# Lora_G_v1_3.net
KiCad netlist of a schematic drawn in EAGLE
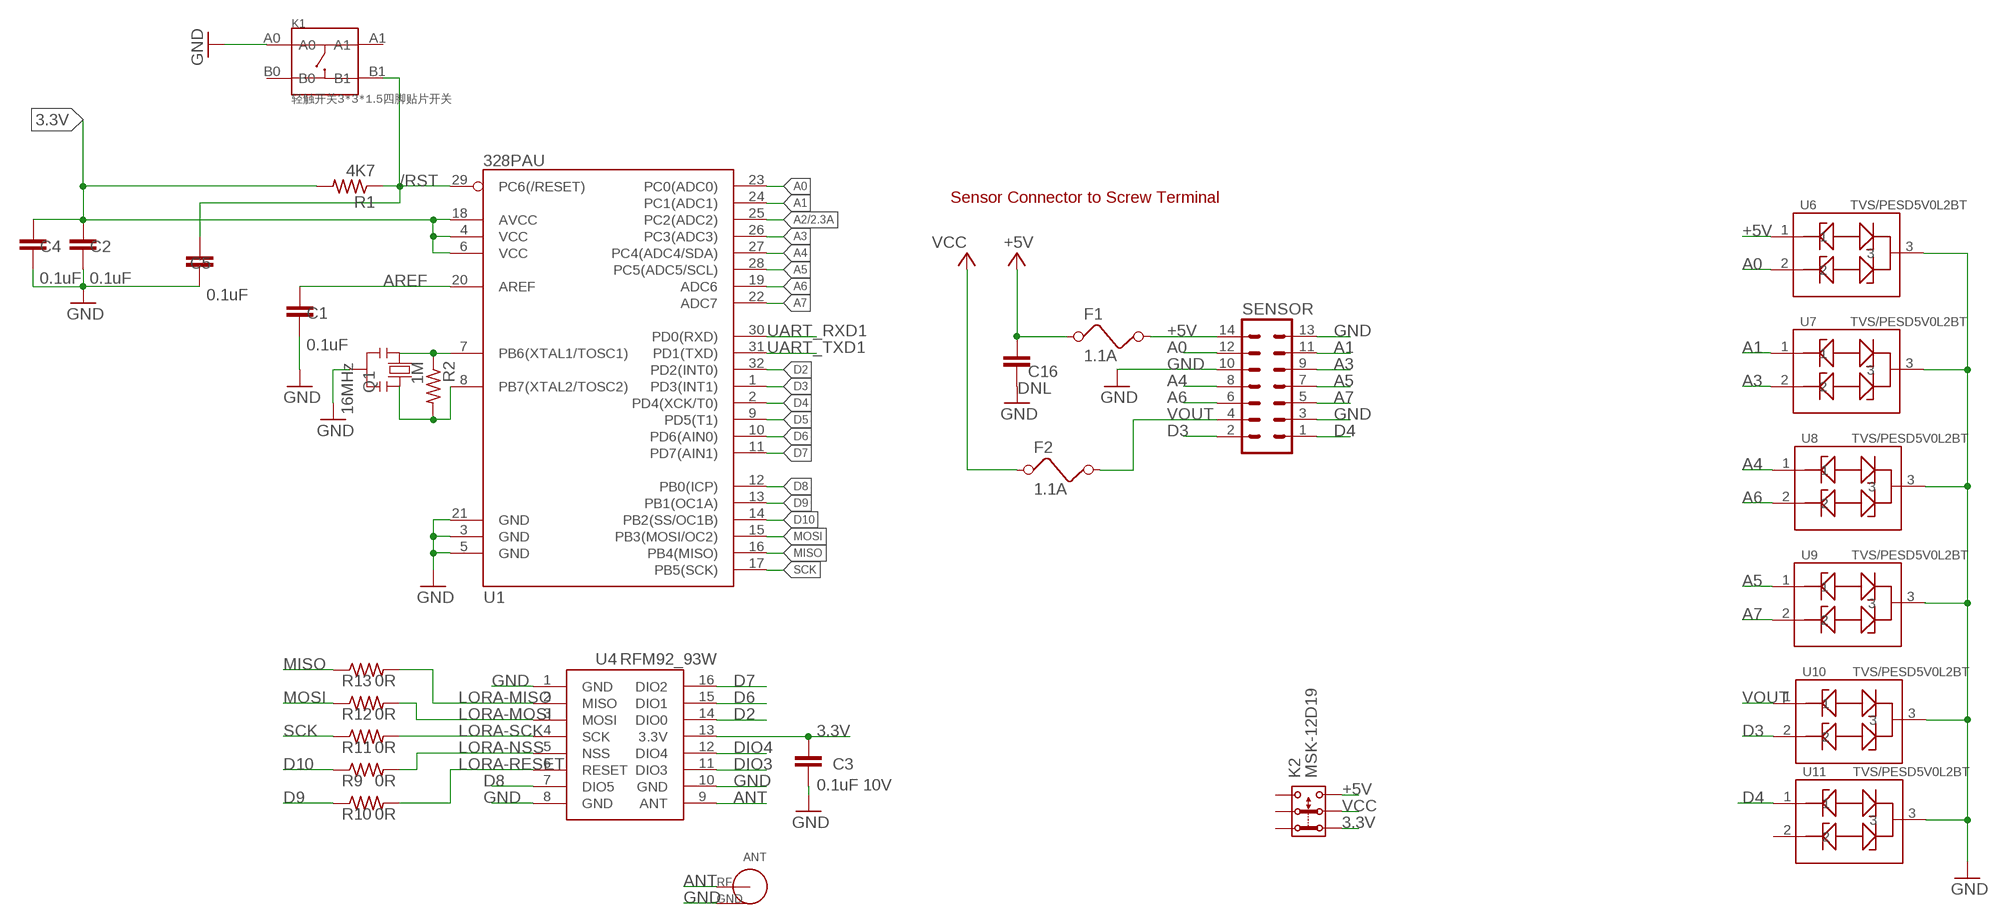
[diagram p0: schematic, sheet 1]
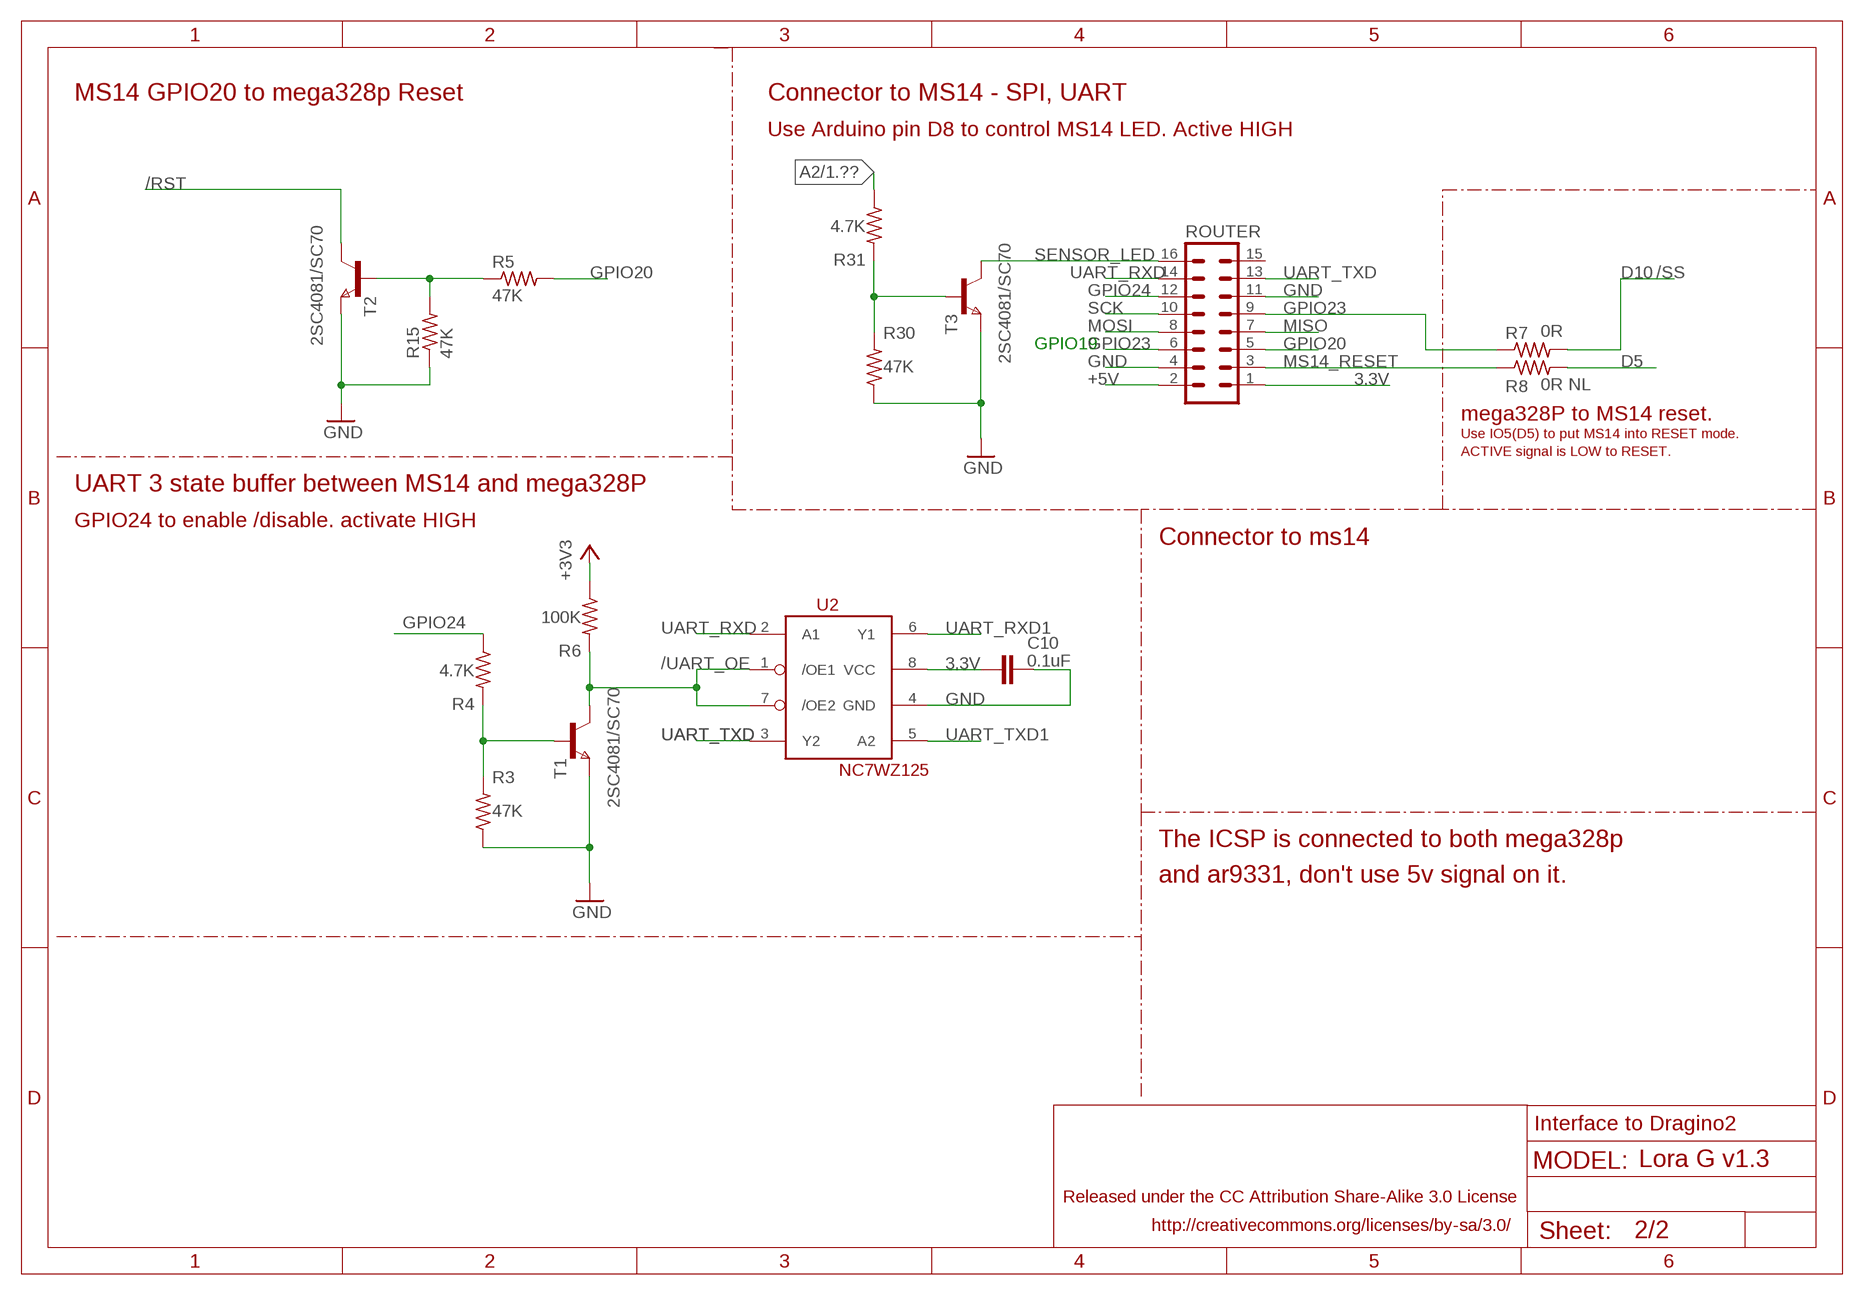
[diagram p1: schematic, sheet 2]

(export (version "E")
  (design (tool "Eeschema 10.0.6"))
  (components
    (comp (ref "C10")
      (value "0.1uF")
      (footprint "eagle-import:C0402")
      (libsource (lib "eagle-import") (part "C-EUC0402"))
    )
    (comp (ref "R3")
      (value "47K")
      (footprint "eagle-import:R0402")
      (libsource (lib "eagle-import") (part "R-US_R0402"))
    )
    (comp (ref "R4")
      (value "4.7K")
      (footprint "eagle-import:R0402")
      (libsource (lib "eagle-import") (part "R-US_R0402"))
    )
    (comp (ref "R5")
      (value "47K")
      (footprint "eagle-import:R0402")
      (libsource (lib "eagle-import") (part "R-US_R0402"))
    )
    (comp (ref "R6")
      (value "100K")
      (footprint "eagle-import:R0402")
      (libsource (lib "eagle-import") (part "R-US_R0402"))
    )
    (comp (ref "R7")
      (value "0R")
      (footprint "eagle-import:R0402")
      (libsource (lib "eagle-import") (part "R-US_R0402"))
    )
    (comp (ref "R8")
      (value "0R NL")
      (footprint "eagle-import:R0805")
      (libsource (lib "eagle-import") (part "R-US_R0805"))
    )
    (comp (ref "R15")
      (value "47K")
      (footprint "eagle-import:R0402")
      (libsource (lib "eagle-import") (part "R-US_R0402"))
    )
    (comp (ref "R30")
      (value "47K")
      (footprint "eagle-import:R0402")
      (libsource (lib "eagle-import") (part "R-US_R0402"))
    )
    (comp (ref "R31")
      (value "4.7K")
      (footprint "eagle-import:R0402")
      (libsource (lib "eagle-import") (part "R-US_R0402"))
    )
    (comp (ref "ROUTER")
      (value "MA08-2")
      (footprint "eagle-import:MA08-2")
      (libsource (lib "eagle-import") (part "MA08-2"))
    )
    (comp (ref "T1")
      (value "2SC4081/SC70")
      (footprint "eagle-import:SOT323")
      (fields (field (name "MPN") "DSS4160U-7"))
      (libsource (lib "eagle-import") (part "NPNSOT323"))
    )
    (comp (ref "T2")
      (value "2SC4081/SC70")
      (footprint "eagle-import:SOT323")
      (fields
        (field (name "MPN") "DSS4160U-7")
        (field (name "MPN_1") "DSS4160U-7")
        (field (name "OC_FARNELL") "1710696")
        (field (name "OC_NEWARK") "25R4558")
      )
      (libsource (lib "eagle-import") (part "NPNSOT323"))
    )
    (comp (ref "T3")
      (value "2SC4081/SC70")
      (footprint "eagle-import:SOT323")
      (fields (field (name "MPN") "DSS4160U-7"))
      (libsource (lib "eagle-import") (part "NPNSOT323"))
    )
    (comp (ref "U2")
      (value "NC7WZ125")
      (footprint "eagle-import:US8")
      (libsource (lib "eagle-import") (part "NC7WZ125"))
    )
    (comp (ref "ANT")
      (value "I-PEX")
      (footprint "eagle-import:I-PEX")
      (libsource (lib "eagle-import") (part "I-PEX"))
    )
    (comp (ref "C1")
      (value "0.1uF")
      (footprint "eagle-import:C0402")
      (libsource (lib "eagle-import") (part "dragino-passive_C-EUC0402"))
    )
    (comp (ref "C2")
      (value "0.1uF")
      (footprint "eagle-import:C0402")
      (libsource (lib "eagle-import") (part "dragino-passive_C-EUC0402"))
    )
    (comp (ref "C3")
      (value "0.1uF 10V")
      (footprint "eagle-import:C0402")
      (libsource (lib "eagle-import") (part "dragino-passive_C-EUC0402"))
    )
    (comp (ref "C4")
      (value "0.1uF")
      (footprint "eagle-import:C0402")
      (libsource (lib "eagle-import") (part "dragino-passive_C-EUC0402"))
    )
    (comp (ref "C5")
      (value "0.1uF")
      (footprint "eagle-import:C0402")
      (libsource (lib "eagle-import") (part "dragino-passive_C-EUC0402"))
    )
    (comp (ref "C16")
      (value "DNL")
      (footprint "eagle-import:C0402")
      (libsource (lib "eagle-import") (part "C-EUC0402"))
    )
    (comp (ref "F1")
      (value "1.1A")
      (footprint "eagle-import:L1812")
      (libsource (lib "eagle-import") (part "FUSE1812"))
    )
    (comp (ref "F2")
      (value "1.1A")
      (footprint "eagle-import:L1812")
      (libsource (lib "eagle-import") (part "FUSE1812"))
    )
    (comp (ref "K1")
      (value "轻触开关3*3*1.5四脚贴片开关")
      (footprint "eagle-import:SW4-SMD-3.35X3.35X1.5MM")
      (libsource (lib "eagle-import") (part "BUTTON-4P-3.3X3.3"))
    )
    (comp (ref "K2")
      (value "MSK-12D19")
      (footprint "eagle-import:MSK-12D19")
      (libsource (lib "eagle-import") (part "MSK-12D19"))
    )
    (comp (ref "Q1")
      (value "16MHz")
      (footprint "eagle-import:RESONATOR")
      (libsource (lib "eagle-import") (part "RESONATORMU"))
    )
    (comp (ref "R1")
      (value "4K7")
      (footprint "eagle-import:R0402")
      (libsource (lib "eagle-import") (part "R-US_R0402"))
    )
    (comp (ref "R2")
      (value "1M")
      (footprint "eagle-import:R0402")
      (libsource (lib "eagle-import") (part "R-US_R0402"))
    )
    (comp (ref "R9")
      (value "0R")
      (footprint "eagle-import:R0402")
      (libsource (lib "eagle-import") (part "R-US_R0402"))
    )
    (comp (ref "R10")
      (value "0R")
      (footprint "eagle-import:R0402")
      (libsource (lib "eagle-import") (part "R-US_R0402"))
    )
    (comp (ref "R11")
      (value "0R")
      (footprint "eagle-import:R0402")
      (libsource (lib "eagle-import") (part "R-US_R0402"))
    )
    (comp (ref "R12")
      (value "0R")
      (footprint "eagle-import:R0402")
      (libsource (lib "eagle-import") (part "R-US_R0402"))
    )
    (comp (ref "R13")
      (value "0R")
      (footprint "eagle-import:R0402")
      (libsource (lib "eagle-import") (part "R-US_R0402"))
    )
    (comp (ref "SENSOR")
      (value "MA07-2")
      (footprint "eagle-import:MA07-2")
      (libsource (lib "eagle-import") (part "MA07-2"))
    )
    (comp (ref "U1")
      (value "328PAU")
      (footprint "eagle-import:328PAU")
      (libsource (lib "eagle-import") (part "328PAU"))
    )
    (comp (ref "U4")
      (value "RFM92_93W")
      (footprint "eagle-import:RFM92_93W")
      (libsource (lib "eagle-import") (part "RFM92_93W"))
    )
    (comp (ref "U6")
      (value "TVS/PESD5V0L2BT")
      (footprint "eagle-import:SOT23")
      (libsource (lib "eagle-import") (part "TVS/PESD5V0L2BT"))
    )
    (comp (ref "U7")
      (value "TVS/PESD5V0L2BT")
      (footprint "eagle-import:SOT23")
      (libsource (lib "eagle-import") (part "TVS/PESD5V0L2BT"))
    )
    (comp (ref "U8")
      (value "TVS/PESD5V0L2BT")
      (footprint "eagle-import:SOT23")
      (libsource (lib "eagle-import") (part "TVS/PESD5V0L2BT"))
    )
    (comp (ref "U9")
      (value "TVS/PESD5V0L2BT")
      (footprint "eagle-import:SOT23")
      (libsource (lib "eagle-import") (part "TVS/PESD5V0L2BT"))
    )
    (comp (ref "U10")
      (value "TVS/PESD5V0L2BT")
      (footprint "eagle-import:SOT23")
      (libsource (lib "eagle-import") (part "TVS/PESD5V0L2BT"))
    )
    (comp (ref "U11")
      (value "TVS/PESD5V0L2BT")
      (footprint "eagle-import:SOT23")
      (libsource (lib "eagle-import") (part "TVS/PESD5V0L2BT"))
    )
  )
  (nets
    (net (code "1") (name "+5V") (class "Default")
      (node (ref "C16") (pin "1") (pinfunction "1_1") (pintype "passive"))
      (node (ref "F1") (pin "1") (pinfunction "1_1") (pintype "passive"))
      (node (ref "K2") (pin "3.2") (pinfunction "3.2_3.2") (pintype "passive"))
      (node (ref "ROUTER") (pin "2") (pinfunction "2_2") (pintype "passive"))
      (node (ref "U6") (pin "1") (pinfunction "1_1") (pintype "bidirectional"))
    )
    (net (code "2") (name "3.3V") (class "Default")
      (node (ref "C10") (pin "2") (pinfunction "2_2") (pintype "passive"))
      (node (ref "C2") (pin "2") (pinfunction "2_2") (pintype "passive"))
      (node (ref "C3") (pin "2") (pinfunction "2_2") (pintype "passive"))
      (node (ref "C4") (pin "2") (pinfunction "2_2") (pintype "passive"))
      (node (ref "K2") (pin "1.2") (pinfunction "1.2_1.2") (pintype "passive"))
      (node (ref "R1") (pin "2") (pinfunction "2_2") (pintype "passive"))
      (node (ref "R6") (pin "1") (pinfunction "1_1") (pintype "passive"))
      (node (ref "ROUTER") (pin "1") (pinfunction "1_1") (pintype "passive"))
      (node (ref "U1") (pin "18") (pinfunction "AVCC_18") (pintype "bidirectional"))
      (node (ref "U1") (pin "4") (pinfunction "VCC_4") (pintype "bidirectional"))
      (node (ref "U1") (pin "6") (pinfunction "VCC_6") (pintype "bidirectional"))
      (node (ref "U2") (pin "8") (pinfunction "VCC_8") (pintype "power_in"))
      (node (ref "U4") (pin "13") (pinfunction "3.3V_13") (pintype "power_in"))
    )
    (net (code "3") (name "A0") (class "Default")
      (node (ref "SENSOR") (pin "12") (pinfunction "12_12") (pintype "passive"))
      (node (ref "U1") (pin "23") (pinfunction "PC0(ADC0)_23") (pintype "bidirectional"))
      (node (ref "U6") (pin "2") (pinfunction "2_2") (pintype "bidirectional"))
    )
    (net (code "4") (name "A1") (class "Default")
      (node (ref "SENSOR") (pin "11") (pinfunction "11_11") (pintype "passive"))
      (node (ref "U1") (pin "24") (pinfunction "PC1(ADC1)_24") (pintype "bidirectional"))
      (node (ref "U7") (pin "1") (pinfunction "1_1") (pintype "bidirectional"))
    )
    (net (code "5") (name "A2") (class "Default")
      (node (ref "R31") (pin "1") (pinfunction "1_1") (pintype "passive"))
      (node (ref "U1") (pin "25") (pinfunction "PC2(ADC2)_25") (pintype "bidirectional"))
    )
    (net (code "6") (name "A3") (class "Default")
      (node (ref "SENSOR") (pin "9") (pinfunction "9_9") (pintype "passive"))
      (node (ref "U1") (pin "26") (pinfunction "PC3(ADC3)_26") (pintype "bidirectional"))
      (node (ref "U7") (pin "2") (pinfunction "2_2") (pintype "bidirectional"))
    )
    (net (code "7") (name "A4") (class "Default")
      (node (ref "SENSOR") (pin "8") (pinfunction "8_8") (pintype "passive"))
      (node (ref "U1") (pin "27") (pinfunction "PC4(ADC4/SDA)_27") (pintype "bidirectional"))
      (node (ref "U8") (pin "1") (pinfunction "1_1") (pintype "bidirectional"))
    )
    (net (code "8") (name "A5") (class "Default")
      (node (ref "SENSOR") (pin "7") (pinfunction "7_7") (pintype "passive"))
      (node (ref "U1") (pin "28") (pinfunction "PC5(ADC5/SCL)_28") (pintype "bidirectional"))
      (node (ref "U9") (pin "1") (pinfunction "1_1") (pintype "bidirectional"))
    )
    (net (code "9") (name "A6") (class "Default")
      (node (ref "SENSOR") (pin "6") (pinfunction "6_6") (pintype "passive"))
      (node (ref "U1") (pin "19") (pinfunction "ADC6_19") (pintype "bidirectional"))
      (node (ref "U8") (pin "2") (pinfunction "2_2") (pintype "bidirectional"))
    )
    (net (code "10") (name "A7") (class "Default")
      (node (ref "SENSOR") (pin "5") (pinfunction "5_5") (pintype "passive"))
      (node (ref "U1") (pin "22") (pinfunction "ADC7_22") (pintype "bidirectional"))
      (node (ref "U9") (pin "2") (pinfunction "2_2") (pintype "bidirectional"))
    )
    (net (code "11") (name "ANT") (class "Default")
      (node (ref "ANT") (pin "SIG") (pinfunction "SIG_SIG") (pintype "passive"))
      (node (ref "U4") (pin "9") (pinfunction "ANT_9") (pintype "bidirectional"))
    )
    (net (code "12") (name "AREF") (class "Default")
      (node (ref "C1") (pin "2") (pinfunction "2_2") (pintype "passive"))
      (node (ref "U1") (pin "20") (pinfunction "AREF_20") (pintype "bidirectional"))
    )
    (net (code "13") (name "D2") (class "Default")
      (node (ref "U1") (pin "32") (pinfunction "PD2(INT0)_32") (pintype "bidirectional"))
      (node (ref "U4") (pin "14") (pinfunction "DIO0_14") (pintype "bidirectional"))
    )
    (net (code "14") (name "D3") (class "Default")
      (node (ref "SENSOR") (pin "2") (pinfunction "2_2") (pintype "passive"))
      (node (ref "U1") (pin "1") (pinfunction "PD3(INT1)_1") (pintype "bidirectional"))
      (node (ref "U10") (pin "2") (pinfunction "2_2") (pintype "bidirectional"))
    )
    (net (code "15") (name "D4") (class "Default")
      (node (ref "SENSOR") (pin "1") (pinfunction "1_1") (pintype "passive"))
      (node (ref "U1") (pin "2") (pinfunction "PD4(XCK/T0)_2") (pintype "bidirectional"))
      (node (ref "U11") (pin "1") (pinfunction "1_1") (pintype "bidirectional"))
    )
    (net (code "16") (name "D5") (class "Default")
      (node (ref "R8") (pin "2") (pinfunction "2_2") (pintype "passive"))
      (node (ref "U1") (pin "9") (pinfunction "PD5(T1)_9") (pintype "bidirectional"))
    )
    (net (code "17") (name "D6") (class "Default")
      (node (ref "U1") (pin "10") (pinfunction "PD6(AIN0)_10") (pintype "bidirectional"))
      (node (ref "U4") (pin "15") (pinfunction "DIO1_15") (pintype "bidirectional"))
    )
    (net (code "18") (name "D7") (class "Default")
      (node (ref "U1") (pin "11") (pinfunction "PD7(AIN1)_11") (pintype "bidirectional"))
      (node (ref "U4") (pin "16") (pinfunction "DIO2_16") (pintype "bidirectional"))
    )
    (net (code "19") (name "D8") (class "Default")
      (node (ref "U1") (pin "12") (pinfunction "PB0(ICP)_12") (pintype "bidirectional"))
      (node (ref "U4") (pin "7") (pinfunction "DIO5_7") (pintype "bidirectional"))
    )
    (net (code "20") (name "D9") (class "Default")
      (node (ref "R10") (pin "1") (pinfunction "1_1") (pintype "passive"))
      (node (ref "U1") (pin "13") (pinfunction "PB1(OC1A)_13") (pintype "bidirectional"))
    )
    (net (code "21") (name "D10") (class "Default")
      (node (ref "R7") (pin "2") (pinfunction "2_2") (pintype "passive"))
      (node (ref "R9") (pin "1") (pinfunction "1_1") (pintype "passive"))
      (node (ref "U1") (pin "14") (pinfunction "PB2(SS/OC1B)_14") (pintype "bidirectional"))
    )
    (net (code "22") (name "DIO3") (class "Default")
      (node (ref "U4") (pin "11") (pinfunction "DIO3_11") (pintype "bidirectional"))
    )
    (net (code "23") (name "DIO4") (class "Default")
      (node (ref "U4") (pin "12") (pinfunction "DIO4_12") (pintype "bidirectional"))
    )
    (net (code "24") (name "GND") (class "Default")
      (node (ref "ANT") (pin "GND") (pinfunction "GND_GND") (pintype "passive"))
      (node (ref "ANT") (pin "GND1") (pinfunction "GND_GND1") (pintype "passive"))
      (node (ref "C1") (pin "1") (pinfunction "1_1") (pintype "passive"))
      (node (ref "C10") (pin "1") (pinfunction "1_1") (pintype "passive"))
      (node (ref "C16") (pin "2") (pinfunction "2_2") (pintype "passive"))
      (node (ref "C2") (pin "1") (pinfunction "1_1") (pintype "passive"))
      (node (ref "C3") (pin "1") (pinfunction "1_1") (pintype "passive"))
      (node (ref "C4") (pin "1") (pinfunction "1_1") (pintype "passive"))
      (node (ref "C5") (pin "1") (pinfunction "1_1") (pintype "passive"))
      (node (ref "K1") (pin "A0") (pinfunction "A0_A0") (pintype "bidirectional"))
      (node (ref "Q1") (pin "2") (pinfunction "2_2") (pintype "passive"))
      (node (ref "R15") (pin "1") (pinfunction "1_1") (pintype "passive"))
      (node (ref "R3") (pin "1") (pinfunction "1_1") (pintype "passive"))
      (node (ref "R30") (pin "1") (pinfunction "1_1") (pintype "passive"))
      (node (ref "ROUTER") (pin "11") (pinfunction "11_11") (pintype "passive"))
      (node (ref "ROUTER") (pin "4") (pinfunction "4_4") (pintype "passive"))
      (node (ref "SENSOR") (pin "10") (pinfunction "10_10") (pintype "passive"))
      (node (ref "SENSOR") (pin "13") (pinfunction "13_13") (pintype "passive"))
      (node (ref "SENSOR") (pin "3") (pinfunction "3_3") (pintype "passive"))
      (node (ref "T1") (pin "3") (pinfunction "E_3") (pintype "passive"))
      (node (ref "T2") (pin "3") (pinfunction "E_3") (pintype "passive"))
      (node (ref "T3") (pin "3") (pinfunction "E_3") (pintype "passive"))
      (node (ref "U1") (pin "21") (pinfunction "GND_21") (pintype "bidirectional"))
      (node (ref "U1") (pin "3") (pinfunction "GND_3") (pintype "bidirectional"))
      (node (ref "U1") (pin "5") (pinfunction "GND_5") (pintype "bidirectional"))
      (node (ref "U10") (pin "3") (pinfunction "3_3") (pintype "bidirectional"))
      (node (ref "U11") (pin "3") (pinfunction "3_3") (pintype "bidirectional"))
      (node (ref "U2") (pin "4") (pinfunction "GND_4") (pintype "power_in"))
      (node (ref "U4") (pin "1") (pinfunction "GND_1") (pintype "power_in"))
      (node (ref "U4") (pin "10") (pinfunction "GND_10") (pintype "power_in"))
      (node (ref "U4") (pin "8") (pinfunction "GND_8") (pintype "power_in"))
      (node (ref "U6") (pin "3") (pinfunction "3_3") (pintype "bidirectional"))
      (node (ref "U7") (pin "3") (pinfunction "3_3") (pintype "bidirectional"))
      (node (ref "U8") (pin "3") (pinfunction "3_3") (pintype "bidirectional"))
      (node (ref "U9") (pin "3") (pinfunction "3_3") (pintype "bidirectional"))
    )
    (net (code "25") (name "GPIO20") (class "Default")
      (node (ref "R5") (pin "2") (pinfunction "2_2") (pintype "passive"))
      (node (ref "ROUTER") (pin "5") (pinfunction "5_5") (pintype "passive"))
    )
    (net (code "26") (name "GPIO23") (class "Default")
      (node (ref "R7") (pin "1") (pinfunction "1_1") (pintype "passive"))
      (node (ref "ROUTER") (pin "6") (pinfunction "6_6") (pintype "passive"))
      (node (ref "ROUTER") (pin "9") (pinfunction "9_9") (pintype "passive"))
    )
    (net (code "27") (name "GPIO24") (class "Default")
      (node (ref "R4") (pin "1") (pinfunction "1_1") (pintype "passive"))
      (node (ref "ROUTER") (pin "12") (pinfunction "12_12") (pintype "passive"))
    )
    (net (code "28") (name "LORA-MISO") (class "Default")
      (node (ref "R13") (pin "2") (pinfunction "2_2") (pintype "passive"))
      (node (ref "U4") (pin "2") (pinfunction "MISO_2") (pintype "bidirectional"))
    )
    (net (code "29") (name "LORA-MOSI") (class "Default")
      (node (ref "R12") (pin "2") (pinfunction "2_2") (pintype "passive"))
      (node (ref "U4") (pin "3") (pinfunction "MOSI_3") (pintype "bidirectional"))
    )
    (net (code "30") (name "LORA-NSS") (class "Default")
      (node (ref "R9") (pin "2") (pinfunction "2_2") (pintype "passive"))
      (node (ref "U4") (pin "5") (pinfunction "NSS_5") (pintype "bidirectional"))
    )
    (net (code "31") (name "LORA-RESET") (class "Default")
      (node (ref "R10") (pin "2") (pinfunction "2_2") (pintype "passive"))
      (node (ref "U4") (pin "6") (pinfunction "RESET_6") (pintype "bidirectional"))
    )
    (net (code "32") (name "LORA-SCK") (class "Default")
      (node (ref "R11") (pin "2") (pinfunction "2_2") (pintype "passive"))
      (node (ref "U4") (pin "4") (pinfunction "SCK_4") (pintype "bidirectional"))
    )
    (net (code "33") (name "MISO") (class "Default")
      (node (ref "R13") (pin "1") (pinfunction "1_1") (pintype "passive"))
      (node (ref "ROUTER") (pin "7") (pinfunction "7_7") (pintype "passive"))
      (node (ref "U1") (pin "16") (pinfunction "PB4(MISO)_16") (pintype "bidirectional"))
    )
    (net (code "34") (name "MOSI") (class "Default")
      (node (ref "R12") (pin "1") (pinfunction "1_1") (pintype "passive"))
      (node (ref "ROUTER") (pin "8") (pinfunction "8_8") (pintype "passive"))
      (node (ref "U1") (pin "15") (pinfunction "PB3(MOSI/OC2)_15") (pintype "bidirectional"))
    )
    (net (code "35") (name "MS14_RESET") (class "Default")
      (node (ref "R8") (pin "1") (pinfunction "1_1") (pintype "passive"))
      (node (ref "ROUTER") (pin "3") (pinfunction "3_3") (pintype "passive"))
    )
    (net (code "36") (name "Net-(F1-Pad2)") (class "Default")
      (node (ref "F1") (pin "2") (pinfunction "2_2") (pintype "passive"))
      (node (ref "SENSOR") (pin "14") (pinfunction "14_14") (pintype "passive"))
    )
    (net (code "37") (name "Net-(T1-B)") (class "Default")
      (node (ref "R3") (pin "2") (pinfunction "2_2") (pintype "passive"))
      (node (ref "R4") (pin "2") (pinfunction "2_2") (pintype "passive"))
      (node (ref "T1") (pin "2") (pinfunction "B_2") (pintype "passive"))
    )
    (net (code "38") (name "Net-(T2-B)") (class "Default")
      (node (ref "R15") (pin "2") (pinfunction "2_2") (pintype "passive"))
      (node (ref "R5") (pin "1") (pinfunction "1_1") (pintype "passive"))
      (node (ref "T2") (pin "2") (pinfunction "B_2") (pintype "passive"))
    )
    (net (code "39") (name "Net-(T3-B)") (class "Default")
      (node (ref "R30") (pin "2") (pinfunction "2_2") (pintype "passive"))
      (node (ref "R31") (pin "2") (pinfunction "2_2") (pintype "passive"))
      (node (ref "T3") (pin "2") (pinfunction "B_2") (pintype "passive"))
    )
    (net (code "40") (name "Net-(U1-PB6(XTAL1{slash}TOSC1))") (class "Default")
      (node (ref "Q1") (pin "1") (pinfunction "1_1") (pintype "passive"))
      (node (ref "R2") (pin "1") (pinfunction "1_1") (pintype "passive"))
      (node (ref "U1") (pin "7") (pinfunction "PB6(XTAL1/TOSC1)_7") (pintype "bidirectional"))
    )
    (net (code "41") (name "Net-(U1-PB7(XTAL2{slash}TOSC2))") (class "Default")
      (node (ref "Q1") (pin "3") (pinfunction "3_3") (pintype "passive"))
      (node (ref "R2") (pin "2") (pinfunction "2_2") (pintype "passive"))
      (node (ref "U1") (pin "8") (pinfunction "PB7(XTAL2/TOSC2)_8") (pintype "bidirectional"))
    )
    (net (code "42") (name "SCK") (class "Default")
      (node (ref "R11") (pin "1") (pinfunction "1_1") (pintype "passive"))
      (node (ref "ROUTER") (pin "10") (pinfunction "10_10") (pintype "passive"))
      (node (ref "U1") (pin "17") (pinfunction "PB5(SCK)_17") (pintype "bidirectional"))
    )
    (net (code "43") (name "SENSOR_LED") (class "Default")
      (node (ref "ROUTER") (pin "16") (pinfunction "16_16") (pintype "passive"))
      (node (ref "T3") (pin "1") (pinfunction "C_1") (pintype "passive"))
    )
    (net (code "44") (name "UART_RXD") (class "Default")
      (node (ref "ROUTER") (pin "14") (pinfunction "14_14") (pintype "passive"))
      (node (ref "U2") (pin "2") (pinfunction "A1_2") (pintype "input"))
    )
    (net (code "45") (name "UART_RXD1") (class "Default")
      (node (ref "U1") (pin "30") (pinfunction "PD0(RXD)_30") (pintype "bidirectional"))
      (node (ref "U2") (pin "6") (pinfunction "Y1_6") (pintype "output"))
    )
    (net (code "46") (name "UART_TXD") (class "Default")
      (node (ref "ROUTER") (pin "13") (pinfunction "13_13") (pintype "passive"))
      (node (ref "U2") (pin "3") (pinfunction "Y2_3") (pintype "output"))
    )
    (net (code "47") (name "UART_TXD1") (class "Default")
      (node (ref "U1") (pin "31") (pinfunction "PD1(TXD)_31") (pintype "bidirectional"))
      (node (ref "U2") (pin "5") (pinfunction "A2_5") (pintype "input"))
    )
    (net (code "48") (name "VCC") (class "Default")
      (node (ref "F2") (pin "1") (pinfunction "1_1") (pintype "passive"))
      (node (ref "K2") (pin "2.2") (pinfunction "2.2_2.2") (pintype "passive"))
    )
    (net (code "49") (name "VOUT") (class "Default")
      (node (ref "F2") (pin "2") (pinfunction "2_2") (pintype "passive"))
      (node (ref "SENSOR") (pin "4") (pinfunction "4_4") (pintype "passive"))
      (node (ref "U10") (pin "1") (pinfunction "1_1") (pintype "bidirectional"))
    )
    (net (code "50") (name "unconnected-(K1-PadA1)") (class "Default")
      (node (ref "K1") (pin "A1") (pinfunction "A1_A1") (pintype "bidirectional"))
    )
    (net (code "51") (name "unconnected-(K1-PadB0)") (class "Default")
      (node (ref "K1") (pin "B0") (pinfunction "B0_B0") (pintype "bidirectional"))
    )
    (net (code "52") (name "unconnected-(K2-Pad1.1)") (class "Default")
      (node (ref "K2") (pin "1.1") (pinfunction "1.1_1.1") (pintype "passive"))
    )
    (net (code "53") (name "unconnected-(K2-Pad2.1)") (class "Default")
      (node (ref "K2") (pin "2.1") (pinfunction "2.1_2.1") (pintype "passive"))
    )
    (net (code "54") (name "unconnected-(K2-Pad3.1)") (class "Default")
      (node (ref "K2") (pin "3.1") (pinfunction "3.1_3.1") (pintype "passive"))
    )
    (net (code "55") (name "unconnected-(ROUTER-Pad15)") (class "Default")
      (node (ref "ROUTER") (pin "15") (pinfunction "15_15") (pintype "passive"))
    )
    (net (code "56") (name "unconnected-(U11-Pad2)") (class "Default")
      (node (ref "U11") (pin "2") (pinfunction "2_2") (pintype "bidirectional"))
    )
    (net (code "57") (name "{slash}RST") (class "Default")
      (node (ref "C5") (pin "2") (pinfunction "2_2") (pintype "passive"))
      (node (ref "K1") (pin "B1") (pinfunction "B1_B1") (pintype "bidirectional"))
      (node (ref "R1") (pin "1") (pinfunction "1_1") (pintype "passive"))
      (node (ref "T2") (pin "1") (pinfunction "C_1") (pintype "passive"))
      (node (ref "U1") (pin "29") (pinfunction "PC6(/RESET)_29") (pintype "bidirectional"))
    )
    (net (code "58") (name "{slash}UART_OE") (class "Default")
      (node (ref "R6") (pin "2") (pinfunction "2_2") (pintype "passive"))
      (node (ref "T1") (pin "1") (pinfunction "C_1") (pintype "passive"))
      (node (ref "U2") (pin "1") (pinfunction "/OE1_1") (pintype "input"))
      (node (ref "U2") (pin "7") (pinfunction "/OE2_7") (pintype "input"))
    )
  )
)
